# Carte_Alim_2019_TOP.net
KiCad netlist of a schematic drawn in Altium Designer
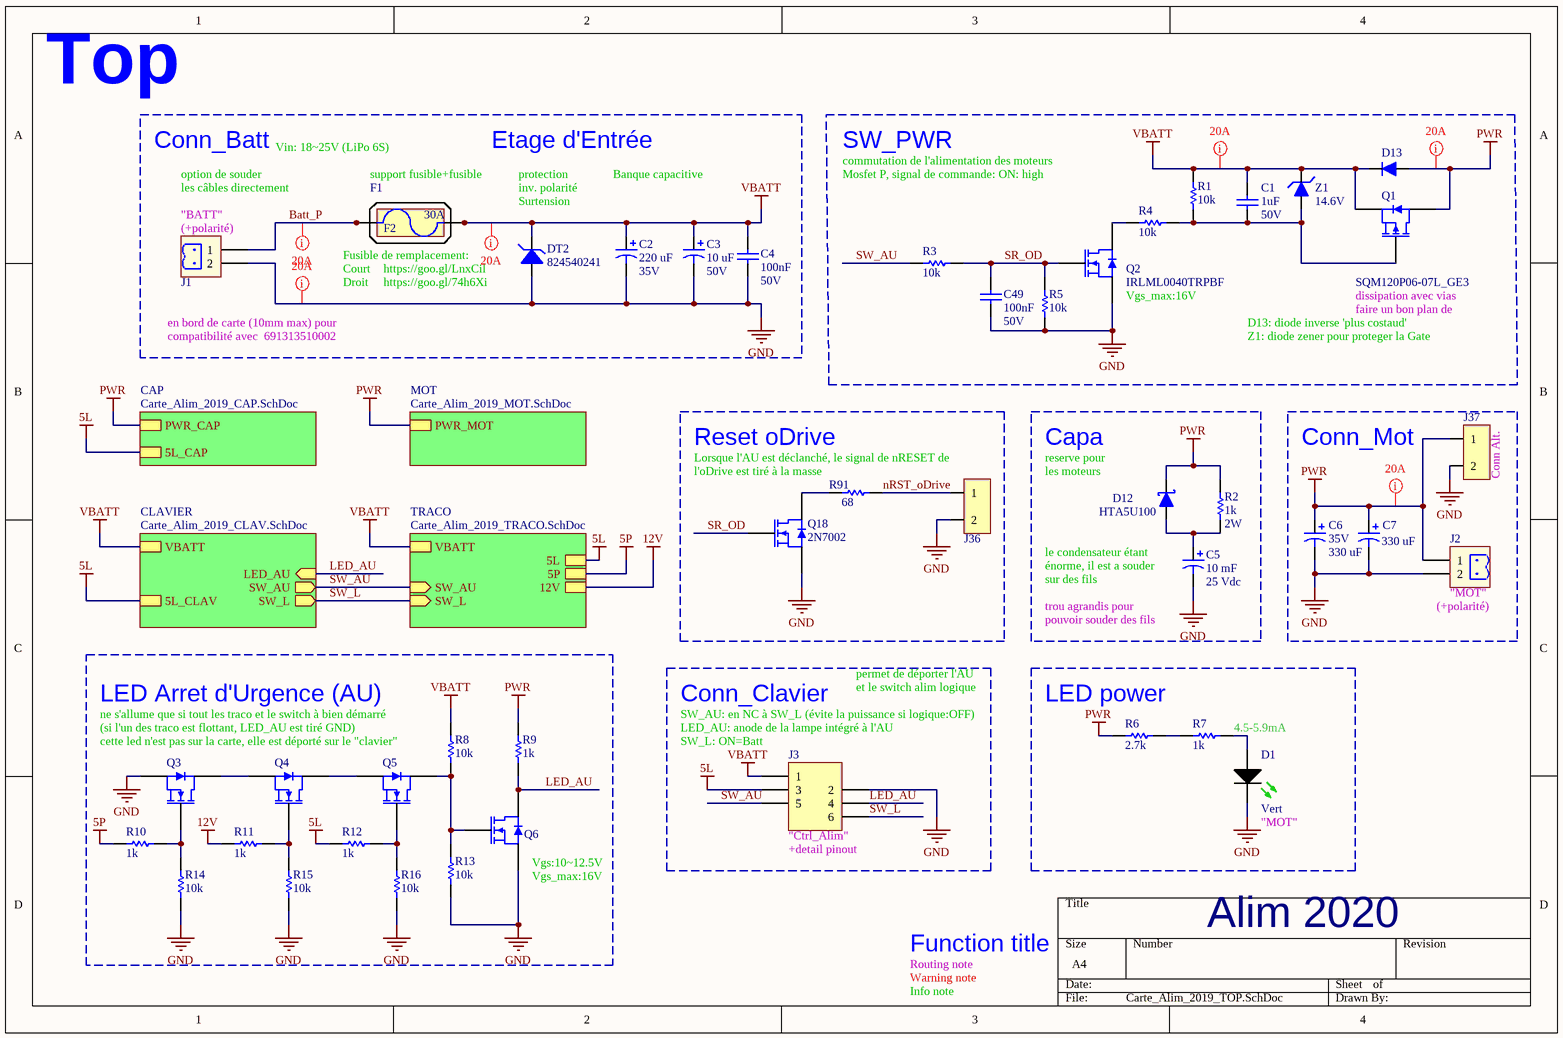
[diagram p0: Carte_Alim_2019_TOP.SchDoc]

(export (version "E")
  (design (tool "Eeschema 10.0.6"))
  (components
    (comp (ref "C1")
      (value "1uF")
      (footprint "WCAP-CSGP_0805, 2x1.25x1.25")
      (description "CAP CER 1uF 50V X7R 0805")
      (fields
        (field (name "MANUFACTURER") "Wurth Elektronik")
        (field (name "MANUFACTURER PART NUMBER") "885012207103")
        (field (name "RATEDVOLTAGE") "50V")
      )
      (libsource (lib "Condensateur") (part "WCAP-CSGP, 885012207103"))
    )
    (comp (ref "C2")
      (value "220 uF")
      (footprint "WCAP-ATG8_8x11.5x3.5x0.5")
      (description "CAP Alu 220 UF 20% 35 V")
      (fields
        (field (name "MANUFACTURER") "Wurth Elektronik")
        (field (name "MANUFACTURER PART NUMBER") "860010574011")
        (field (name "RATEDVOLTAGE") "35V")
      )
      (libsource (lib "Condensateur") (part "WCAP-ATG8, 860010574011"))
    )
    (comp (ref "C3")
      (value "10 uF")
      (footprint "WCAP-ATG8_5x11x2x0.5")
      (description "CAP Alu 10 UF 20% 50 V")
      (fields
        (field (name "RATEDVOLTAGE") "50V")
        (field (name "MANUFACTURER") "Wurth Elektronik")
        (field (name "MANUFACTURER PART NUMBER") "860010672009")
      )
      (libsource (lib "Condensateur") (part "WCAP-ATG8, 860010672009"))
    )
    (comp (ref "C4")
      (value "100nF")
      (footprint "WCAP-CSGP_0603, 1.6x0.8x0.8")
      (description "CAP CER 100nF 50V X7R 0603")
      (fields
        (field (name "RATEDVOLTAGE") "50V")
        (field (name "MANUFACTURER") "Wurth Elektronik")
        (field (name "MANUFACTURER PART NUMBER") "885012206095")
      )
      (libsource (lib "Condensateur") (part "WCAP-CSGP, 885012206095"))
    )
    (comp (ref "C5")
      (value "10 mF")
      (footprint "WCAP-ATG8_22x41x10x0.8")
      (description "CAP Alu 10'000 UF 25 V")
      (fields
        (field (name "MANUFACTURER PART NUMBER") "860010483029")
        (field (name "MANUFACTURER") "Wurth Elektronik")
        (field (name "RATED VOLTAGE") "25 Vdc")
      )
      (libsource (lib "Condensateur") (part "WCAP-ATG8, 860010483029"))
    )
    (comp (ref "C6")
      (value "330 uF")
      (footprint "WCAP-ATG8_10x12.5x5x0.6")
      (description "CAP Alu 330 UF 20% 35 V")
      (fields
        (field (name "MANUFACTURER") "Wurth Elektronik")
        (field (name "MANUFACTURER PART NUMBER") "860010575012")
        (field (name "RATEDVOLTAGE") "35V")
      )
      (libsource (lib "Condensateur") (part "WCAP-ATG8, 860010575012"))
    )
    (comp (ref "C7")
      (value "330 uF")
      (footprint "WCAP-ATG8_10x12.5x5x0.6")
      (description "CAP Alu 330 UF 20% 35 V")
      (fields
        (field (name "MANUFACTURER") "Wurth Elektronik")
        (field (name "MANUFACTURER PART NUMBER") "860010575012")
      )
      (libsource (lib "Condensateur") (part "WCAP-ATG8, 860010575012"))
    )
    (comp (ref "C49")
      (value "100nF")
      (footprint "WCAP-CSGP_0603, 1.6x0.8x0.8")
      (description "CAP CER 100nF 50V X7R 0603")
      (fields
        (field (name "RATEDVOLTAGE") "50V")
        (field (name "MANUFACTURER") "Wurth Elektronik")
        (field (name "MANUFACTURER PART NUMBER") "885012206095")
      )
      (libsource (lib "Condensateur") (part "WCAP-CSGP, 885012206095"))
    )
    (comp (ref "D1")
      (value "Vert")
      (footprint "SMCW_0603")
      (description "SMD mono-color Chip LED, WL-SMCW, Green")
      (fields
        (field (name "MANUFACTURER PART NUMBER") "150060GS75000")
        (field (name "CREATED BY") "Christin Otto")
      )
      (libsource (lib "Optoélectronique") (part "WL-SMCW 0603  150060GS75000"))
    )
    (comp (ref "D12")
      (value "HTA5U100")
      (footprint "SMA Diode (DO-214AC)")
      (description "DIODE SCHOTTKY 100V 5A SMA (DO-214AC)")
      (fields (field (name "MANUFACTURER") "MULTICOMP"))
      (libsource (lib "Diode") (part "HTA5U100"))
    )
    (comp (ref "D13")
      (value "RS3J R6")
      (footprint "DO-214AB_Unidirectional")
      (description "DIODE GEN PURP 600V 3A SMC")
      (fields (field (name "MANUFACTURER") "TAIWAN SEMICONDUCTOR"))
      (libsource (lib "Diode") (part "RS3J_R6"))
    )
    (comp (ref "DT2")
      (value "824540241")
      (footprint "DO-214AB_Unidirectional")
      (description "WE-TVSP Power TVS Diode, Unidirectional, 1500 W, 24 VDC")
      (fields (field (name "MANUFACTURER") "Wurth Electronics Inc."))
      (libsource (lib "Diode") (part "824540241"))
    )
    (comp (ref "F1")
      (value "3557-2")
      (footprint "3557-2")
      (description "FUSE Holder 500V 30A PCB")
      (fields (field (name "MANUFACTURER") "Keystone Electronics"))
      (libsource (lib "Fuse") (part "3557-2"))
    )
    (comp (ref "F2")
      (value "0891030.NXS")
      (description "FUSE AUTO 30A 58VDC BLADE MINI")
      (fields (field (name "MANUFACTURER") "Littelfuse Inc.") (field (name "COURANT NOMINAL") "30A"))
      (libsource (lib "Fuse") (part "0891030.NXS"))
    )
    (comp (ref "J1")
      (value "691311500102")
      (footprint "691311500102")
      (description "WR-TBL 2p Series 311 - 5.08 mm Closed Vertical PCB Header")
      (fields (field (name "MANUFACTURER") "Wurth Electronics Inc."))
      (libsource (lib "") (part "691311500102_1"))
    )
    (comp (ref "J2")
      (value "691311500102")
      (footprint "691311500102")
      (description "WR-TBL 2p Series 311 - 5.08 mm Closed Vertical PCB Header")
      (fields (field (name "MANUFACTURER") "Wurth Electronics Inc."))
      (libsource (lib "Connecteurs") (part "691311500102"))
    )
    (comp (ref "J3")
      (value "690367280676")
      (footprint "690367280676")
      (description "WR-MM 6p Female SMT Connector with Polarization")
      (fields (field (name "MANUFACTURER") "Wurth Electronics Inc."))
      (libsource (lib "Connecteurs") (part "690367280676"))
    )
    (comp (ref "J36")
      (value "22-03-2021")
      (footprint "22-03-2021")
      (libsource (lib "Connecteurs") (part "22-03-2021"))
    )
    (comp (ref "J37")
      (value "22-03-2021")
      (footprint "22-03-2021")
      (libsource (lib "Connecteurs") (part "22-03-2021"))
    )
    (comp (ref "Q1")
      (value "SQM120P06-07L_GE3")
      (footprint "TO-263")
      (description "MOSFET P 60V 120A D2PAK")
      (fields (field (name "MANUFACTURER") "VISHAY"))
      (libsource (lib "Transistors") (part "SQM120P06-07L_GE3"))
    )
    (comp (ref "Q2")
      (value "IRLML0040TRPBF")
      (footprint "SOT-23")
      (description "MOSFET N 40V 3.6A SOT23")
      (fields (field (name "MANUFACTURER") "INTERNATIONAL RECTIFIER"))
      (libsource (lib "Transistors") (part "IRLML0040"))
    )
    (comp (ref "Q3")
      (value "IRLML0040TRPBF")
      (footprint "SOT-23")
      (description "MOSFET N 40V 3.6A SOT23")
      (fields (field (name "MANUFACTURER") "INTERNATIONAL RECTIFIER"))
      (libsource (lib "Transistors") (part "IRLML0040"))
    )
    (comp (ref "Q4")
      (value "IRLML0040TRPBF")
      (footprint "SOT-23")
      (description "MOSFET N 40V 3.6A SOT23")
      (fields (field (name "MANUFACTURER") "INTERNATIONAL RECTIFIER"))
      (libsource (lib "Transistors") (part "IRLML0040"))
    )
    (comp (ref "Q5")
      (value "IRLML0040TRPBF")
      (footprint "SOT-23")
      (description "MOSFET N 40V 3.6A SOT23")
      (fields (field (name "MANUFACTURER") "INTERNATIONAL RECTIFIER"))
      (libsource (lib "Transistors") (part "IRLML0040"))
    )
    (comp (ref "Q6")
      (value "IRLML0040TRPBF")
      (footprint "SOT-23")
      (description "MOSFET N 40V 3.6A SOT23")
      (fields (field (name "MANUFACTURER") "INTERNATIONAL RECTIFIER"))
      (libsource (lib "Transistors") (part "IRLML0040"))
    )
    (comp (ref "Q18")
      (value "2N7002")
      (footprint "SOT-23")
      (description "MOSFET N 60V 115MA SOT-23")
      (fields (field (name "MANUFACTURER") "Changjiang Electronics Tech (CJ)"))
      (libsource (lib "Transistors") (part "2N7002"))
    )
    (comp (ref "R1")
      (value "10k")
      (footprint "RESC1608X06N")
      (description "RES SMD 10K OHM 1% 1/10W 0603")
      (fields
        (field (name "MANUFACTURER") "Yageo")
        (field (name "MANUFACTURER PART NUMBER") "RC0603FR-0710KL")
      )
      (libsource (lib "Resistance") (part "RC0603FR-0710KL"))
    )
    (comp (ref "R2")
      (value "1k")
      (footprint "RESADV480W80L1200D390")
      (description "resistance traversante verticale générique")
      (fields
        (field (name "MANUFACTURER") "MULTICOMP")
        (field (name "MANUFACTURER PART NUMBER") "MCKNP02WJ0102A19")
        (field (name "POWER") "2W")
      )
      (libsource (lib "Resistance") (part "Generic_TH_Vert_Res"))
    )
    (comp (ref "R3")
      (value "10k")
      (footprint "RESC1608X06N")
      (description "RES SMD 10K OHM 1% 1/10W 0603")
      (fields
        (field (name "MANUFACTURER") "Yageo")
        (field (name "MANUFACTURER PART NUMBER") "RC0603FR-0710KL")
      )
      (libsource (lib "Resistance") (part "RC0603FR-0710KL"))
    )
    (comp (ref "R4")
      (value "10k")
      (footprint "RESC1608X06N")
      (description "RES SMD 10K OHM 1% 1/10W 0603")
      (fields
        (field (name "MANUFACTURER") "Yageo")
        (field (name "MANUFACTURER PART NUMBER") "RC0603FR-0710KL")
      )
      (libsource (lib "Resistance") (part "RC0603FR-0710KL"))
    )
    (comp (ref "R5")
      (value "10k")
      (footprint "RESC1608X06N")
      (description "RES SMD 10K OHM 1% 1/10W 0603")
      (fields
        (field (name "MANUFACTURER") "Yageo")
        (field (name "MANUFACTURER PART NUMBER") "RC0603FR-0710KL")
      )
      (libsource (lib "Resistance") (part "RC0603FR-0710KL"))
    )
    (comp (ref "R6")
      (value "2.7k")
      (footprint "RESC2012X06M")
      (description "RES SMD 2K7 OHM 1% 1/8W 0805")
      (fields
        (field (name "MANUFACTURER") "Yageo")
        (field (name "MANUFACTURER PART NUMBER") "RC0805FR-072K7L")
      )
      (libsource (lib "Resistance") (part "RC0805FR-072K7L"))
    )
    (comp (ref "R7")
      (value "1k")
      (footprint "RESC1608X06N")
      (description "RES SMD 1K OHM 1% 1/10W 0603")
      (fields
        (field (name "MANUFACTURER") "Yageo")
        (field (name "MANUFACTURER PART NUMBER") "RC0603FR-071KL")
      )
      (libsource (lib "Resistance") (part "RC0603FR-071KL"))
    )
    (comp (ref "R8")
      (value "10k")
      (footprint "RESC1608X06N")
      (description "RES SMD 10K OHM 1% 1/10W 0603")
      (fields
        (field (name "MANUFACTURER") "Yageo")
        (field (name "MANUFACTURER PART NUMBER") "RC0603FR-0710KL")
      )
      (libsource (lib "Resistance") (part "RC0603FR-0710KL"))
    )
    (comp (ref "R9")
      (value "1k")
      (footprint "RESC1608X06N")
      (description "RES SMD 1K OHM 1% 1/10W 0603")
      (fields
        (field (name "MANUFACTURER") "Yageo")
        (field (name "MANUFACTURER PART NUMBER") "RC0603FR-071KL")
      )
      (libsource (lib "Resistance") (part "RC0603FR-071KL"))
    )
    (comp (ref "R10")
      (value "1k")
      (footprint "RESC1608X06N")
      (description "RES SMD 1K OHM 1% 1/10W 0603")
      (fields
        (field (name "MANUFACTURER") "Yageo")
        (field (name "MANUFACTURER PART NUMBER") "RC0603FR-071KL")
      )
      (libsource (lib "Resistance") (part "RC0603FR-071KL"))
    )
    (comp (ref "R11")
      (value "1k")
      (footprint "RESC1608X06N")
      (description "RES SMD 1K OHM 1% 1/10W 0603")
      (fields
        (field (name "MANUFACTURER") "Yageo")
        (field (name "MANUFACTURER PART NUMBER") "RC0603FR-071KL")
      )
      (libsource (lib "Resistance") (part "RC0603FR-071KL"))
    )
    (comp (ref "R12")
      (value "1k")
      (footprint "RESC1608X06N")
      (description "RES SMD 1K OHM 1% 1/10W 0603")
      (fields
        (field (name "MANUFACTURER") "Yageo")
        (field (name "MANUFACTURER PART NUMBER") "RC0603FR-071KL")
      )
      (libsource (lib "Resistance") (part "RC0603FR-071KL"))
    )
    (comp (ref "R13")
      (value "10k")
      (footprint "RESC1608X06N")
      (description "RES SMD 10K OHM 1% 1/10W 0603")
      (fields
        (field (name "MANUFACTURER") "Yageo")
        (field (name "MANUFACTURER PART NUMBER") "RC0603FR-0710KL")
      )
      (libsource (lib "Resistance") (part "RC0603FR-0710KL"))
    )
    (comp (ref "R14")
      (value "10k")
      (footprint "RESC1608X06N")
      (description "RES SMD 10K OHM 1% 1/10W 0603")
      (fields
        (field (name "MANUFACTURER") "Yageo")
        (field (name "MANUFACTURER PART NUMBER") "RC0603FR-0710KL")
      )
      (libsource (lib "Resistance") (part "RC0603FR-0710KL"))
    )
    (comp (ref "R15")
      (value "10k")
      (footprint "RESC1608X06N")
      (description "RES SMD 10K OHM 1% 1/10W 0603")
      (fields
        (field (name "MANUFACTURER") "Yageo")
        (field (name "MANUFACTURER PART NUMBER") "RC0603FR-0710KL")
      )
      (libsource (lib "Resistance") (part "RC0603FR-0710KL"))
    )
    (comp (ref "R16")
      (value "10k")
      (footprint "RESC1608X06N")
      (description "RES SMD 10K OHM 1% 1/10W 0603")
      (fields
        (field (name "MANUFACTURER") "Yageo")
        (field (name "MANUFACTURER PART NUMBER") "RC0603FR-0710KL")
      )
      (libsource (lib "Resistance") (part "RC0603FR-0710KL"))
    )
    (comp (ref "R91")
      (value "68")
      (footprint "RESC1608X06N")
      (description "RES SMD 68 OHM 1% 1/10W 0603")
      (fields
        (field (name "MANUFACTURER") "Yageo")
        (field (name "MANUFACTURER PART NUMBER") "RC0603FR-0768RL")
      )
      (libsource (lib "Resistance") (part "RC0603FR-0768RL"))
    )
    (comp (ref "Z1")
      (value "14.6V")
      (footprint "SOD-323")
      (description "DIODE ZENER 14.6V 300mW SOD323")
      (fields
        (field (name "MANUFACTURER") "ON Semiconductor")
        (field (name "MANUFACTURER PART NUMBER") "MM3Z15VST1G")
      )
      (libsource (lib "Diode") (part "MM3Z15VST1G"))
    )
  )
  (nets
    (net (code "1") (name "/Batt_P") (class "Default")
      (node (ref "F1") (pin "1") (pinfunction "1_1") (pintype "passive"))
      (node (ref "F1") (pin "3") (pinfunction "3_3") (pintype "passive"))
      (node (ref "J1") (pin "1") (pinfunction "1_1") (pintype "passive"))
    )
    (net (code "2") (name "/LED_AU") (class "Default")
      (node (ref "J3") (pin "4") (pinfunction "4_4") (pintype "passive"))
      (node (ref "Q6") (pin "3") (pinfunction "D_3") (pintype "passive"))
      (node (ref "R9") (pin "1") (pinfunction "1_1") (pintype "passive"))
    )
    (net (code "3") (name "/SR_OD") (class "Default")
      (node (ref "C49") (pin "2") (pinfunction "2_2") (pintype "passive"))
      (node (ref "Q18") (pin "1") (pinfunction "G_1") (pintype "passive"))
      (node (ref "Q2") (pin "1") (pinfunction "G_1") (pintype "passive"))
      (node (ref "R3") (pin "2") (pinfunction "2_2") (pintype "passive"))
      (node (ref "R5") (pin "1") (pinfunction "1_1") (pintype "passive"))
    )
    (net (code "4") (name "/SW_AU") (class "Default")
      (node (ref "J3") (pin "5") (pinfunction "5_5") (pintype "passive"))
      (node (ref "R3") (pin "1") (pinfunction "1_1") (pintype "passive"))
    )
    (net (code "5") (name "/SW_L") (class "Default")
      (node (ref "J3") (pin "6") (pinfunction "6_6") (pintype "passive"))
    )
    (net (code "6") (name "/nRST_oDrive") (class "Default")
      (node (ref "J36") (pin "1") (pinfunction "1_1") (pintype "passive"))
      (node (ref "R91") (pin "2") (pinfunction "2_2") (pintype "passive"))
    )
    (net (code "7") (name "5L") (class "Default")
      (node (ref "J3") (pin "3") (pinfunction "3_3") (pintype "passive"))
      (node (ref "R12") (pin "2") (pinfunction "2_2") (pintype "passive"))
    )
    (net (code "8") (name "5P") (class "Default")
      (node (ref "R10") (pin "2") (pinfunction "2_2") (pintype "passive"))
    )
    (net (code "9") (name "12V") (class "Default")
      (node (ref "R11") (pin "2") (pinfunction "2_2") (pintype "passive"))
    )
    (net (code "10") (name "GND") (class "Default")
      (node (ref "C2") (pin "2") (pinfunction "2_2") (pintype "passive"))
      (node (ref "C3") (pin "2") (pinfunction "2_2") (pintype "passive"))
      (node (ref "C4") (pin "1") (pinfunction "1_1") (pintype "passive"))
      (node (ref "C49") (pin "1") (pinfunction "1_1") (pintype "passive"))
      (node (ref "C5") (pin "2") (pinfunction "2_2") (pintype "passive"))
      (node (ref "C6") (pin "2") (pinfunction "2_2") (pintype "passive"))
      (node (ref "C7") (pin "2") (pinfunction "2_2") (pintype "passive"))
      (node (ref "D1") (pin "1") (pinfunction "C_1") (pintype "passive"))
      (node (ref "DT2") (pin "1") (pintype "passive"))
      (node (ref "J1") (pin "2") (pinfunction "2_2") (pintype "passive"))
      (node (ref "J2") (pin "2") (pinfunction "2_2") (pintype "passive"))
      (node (ref "J3") (pin "2") (pinfunction "2_2") (pintype "passive"))
      (node (ref "J36") (pin "2") (pinfunction "2_2") (pintype "passive"))
      (node (ref "J37") (pin "2") (pinfunction "2_2") (pintype "passive"))
      (node (ref "Q18") (pin "2") (pinfunction "S_2") (pintype "passive"))
      (node (ref "Q2") (pin "2") (pinfunction "S_2") (pintype "passive"))
      (node (ref "Q3") (pin "2") (pinfunction "S_2") (pintype "passive"))
      (node (ref "Q6") (pin "2") (pinfunction "S_2") (pintype "passive"))
      (node (ref "R13") (pin "1") (pinfunction "1_1") (pintype "passive"))
      (node (ref "R14") (pin "1") (pinfunction "1_1") (pintype "passive"))
      (node (ref "R15") (pin "1") (pinfunction "1_1") (pintype "passive"))
      (node (ref "R16") (pin "1") (pinfunction "1_1") (pintype "passive"))
      (node (ref "R5") (pin "2") (pinfunction "2_2") (pintype "passive"))
    )
    (net (code "11") (name "Net-(C5-Pad1)") (class "Default")
      (node (ref "C5") (pin "1") (pinfunction "1_1") (pintype "passive"))
      (node (ref "D12") (pin "1") (pintype "passive"))
      (node (ref "R2") (pin "2") (pinfunction "2_2") (pintype "passive"))
    )
    (net (code "12") (name "Net-(D1-A)") (class "Default")
      (node (ref "D1") (pin "2") (pinfunction "A_2") (pintype "passive"))
      (node (ref "R7") (pin "1") (pinfunction "1_1") (pintype "passive"))
    )
    (net (code "13") (name "Net-(Q1-G)") (class "Default")
      (node (ref "C1") (pin "1") (pinfunction "1_1") (pintype "passive"))
      (node (ref "Q1") (pin "1") (pinfunction "G_1") (pintype "passive"))
      (node (ref "R1") (pin "1") (pinfunction "1_1") (pintype "passive"))
      (node (ref "R4") (pin "1") (pinfunction "1_1") (pintype "passive"))
      (node (ref "Z1") (pin "1") (pintype "passive"))
    )
    (net (code "14") (name "Net-(Q2-D)") (class "Default")
      (node (ref "Q2") (pin "3") (pinfunction "D_3") (pintype "passive"))
      (node (ref "R4") (pin "2") (pinfunction "2_2") (pintype "passive"))
    )
    (net (code "15") (name "Net-(Q3-D)") (class "Default")
      (node (ref "Q3") (pin "3") (pinfunction "D_3") (pintype "passive"))
      (node (ref "Q4") (pin "2") (pinfunction "S_2") (pintype "passive"))
    )
    (net (code "16") (name "Net-(Q3-G)") (class "Default")
      (node (ref "Q3") (pin "1") (pinfunction "G_1") (pintype "passive"))
      (node (ref "R10") (pin "1") (pinfunction "1_1") (pintype "passive"))
      (node (ref "R14") (pin "2") (pinfunction "2_2") (pintype "passive"))
    )
    (net (code "17") (name "Net-(Q4-D)") (class "Default")
      (node (ref "Q4") (pin "3") (pinfunction "D_3") (pintype "passive"))
      (node (ref "Q5") (pin "2") (pinfunction "S_2") (pintype "passive"))
    )
    (net (code "18") (name "Net-(Q4-G)") (class "Default")
      (node (ref "Q4") (pin "1") (pinfunction "G_1") (pintype "passive"))
      (node (ref "R11") (pin "1") (pinfunction "1_1") (pintype "passive"))
      (node (ref "R15") (pin "2") (pinfunction "2_2") (pintype "passive"))
    )
    (net (code "19") (name "Net-(Q5-D)") (class "Default")
      (node (ref "Q5") (pin "3") (pinfunction "D_3") (pintype "passive"))
      (node (ref "Q6") (pin "1") (pinfunction "G_1") (pintype "passive"))
      (node (ref "R13") (pin "2") (pinfunction "2_2") (pintype "passive"))
      (node (ref "R8") (pin "1") (pinfunction "1_1") (pintype "passive"))
    )
    (net (code "20") (name "Net-(Q5-G)") (class "Default")
      (node (ref "Q5") (pin "1") (pinfunction "G_1") (pintype "passive"))
      (node (ref "R12") (pin "1") (pinfunction "1_1") (pintype "passive"))
      (node (ref "R16") (pin "2") (pinfunction "2_2") (pintype "passive"))
    )
    (net (code "21") (name "Net-(Q18-D)") (class "Default")
      (node (ref "Q18") (pin "3") (pinfunction "D_3") (pintype "passive"))
      (node (ref "R91") (pin "1") (pinfunction "1_1") (pintype "passive"))
    )
    (net (code "22") (name "Net-(R6-Pad2)") (class "Default")
      (node (ref "R6") (pin "2") (pinfunction "2_2") (pintype "passive"))
      (node (ref "R7") (pin "2") (pinfunction "2_2") (pintype "passive"))
    )
    (net (code "23") (name "PWR") (class "Default")
      (node (ref "C6") (pin "1") (pinfunction "1_1") (pintype "passive"))
      (node (ref "C7") (pin "1") (pinfunction "1_1") (pintype "passive"))
      (node (ref "D12") (pin "2") (pintype "passive"))
      (node (ref "D13") (pin "1") (pintype "passive"))
      (node (ref "J2") (pin "1") (pinfunction "1_1") (pintype "passive"))
      (node (ref "J37") (pin "1") (pinfunction "1_1") (pintype "passive"))
      (node (ref "Q1") (pin "4") (pinfunction "D_4") (pintype "passive"))
      (node (ref "R2") (pin "1") (pinfunction "1_1") (pintype "passive"))
      (node (ref "R6") (pin "1") (pinfunction "1_1") (pintype "passive"))
      (node (ref "R9") (pin "2") (pinfunction "2_2") (pintype "passive"))
    )
    (net (code "24") (name "VBATT") (class "Default")
      (node (ref "C1") (pin "2") (pinfunction "2_2") (pintype "passive"))
      (node (ref "C2") (pin "1") (pinfunction "1_1") (pintype "passive"))
      (node (ref "C3") (pin "1") (pinfunction "1_1") (pintype "passive"))
      (node (ref "C4") (pin "2") (pinfunction "2_2") (pintype "passive"))
      (node (ref "D13") (pin "2") (pintype "passive"))
      (node (ref "DT2") (pin "2") (pintype "passive"))
      (node (ref "F1") (pin "2") (pinfunction "2_2") (pintype "passive"))
      (node (ref "F1") (pin "4") (pinfunction "4_4") (pintype "passive"))
      (node (ref "J3") (pin "1") (pinfunction "1_1") (pintype "passive"))
      (node (ref "Q1") (pin "3") (pinfunction "S_3") (pintype "passive"))
      (node (ref "R1") (pin "2") (pinfunction "2_2") (pintype "passive"))
      (node (ref "R8") (pin "2") (pinfunction "2_2") (pintype "passive"))
      (node (ref "Z1") (pin "2") (pintype "passive"))
    )
  )
)
